# UARTSTM.net
KiCad netlist of a schematic drawn in Altium Designer
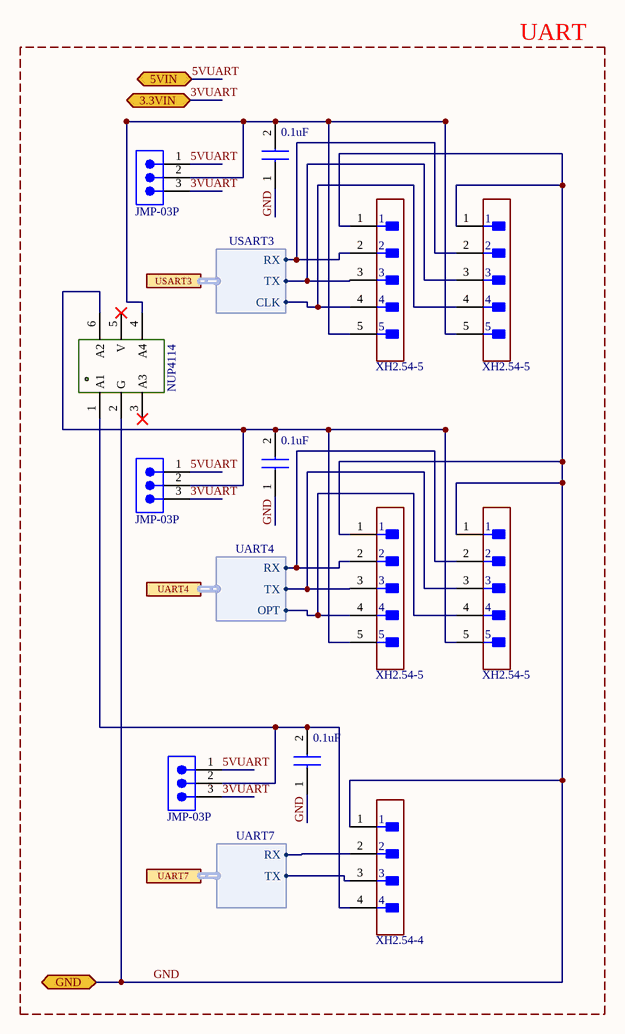
[diagram p0: UARTSTM.SchDoc]

(export (version "E")
  (design (tool "Eeschema 10.0.6"))
  (components
    (comp (ref "CAPUART3")
      (value "0.1uF")
      (footprint "CAP0805")
      (description "CAP-SMD0805")
      (libsource (lib "Components_Robots") (part "CAP0805"))
    )
    (comp (ref "CAPUART4")
      (value "0.1uF")
      (footprint "CAP0805")
      (description "CAP-SMD0805")
      (libsource (lib "Components_Robots") (part "CAP0805"))
    )
    (comp (ref "CAPUART7")
      (value "0.1uF")
      (footprint "CAP0805")
      (description "CAP-SMD0805")
      (libsource (lib "Components_Robots") (part "CAP0805"))
    )
    (comp (ref "JMPUART3")
      (value "JMP-03P")
      (footprint "JMP-03P")
      (description "PLS-1x3")
      (libsource (lib "Components_Robots") (part "JMP-03P"))
    )
    (comp (ref "JMPUART4")
      (value "JMP-03P")
      (footprint "JMP-03P")
      (description "PLS-1x3")
      (libsource (lib "Components_Robots") (part "JMP-03P"))
    )
    (comp (ref "JMPUART7")
      (value "JMP-03P")
      (footprint "JMP-03P")
      (description "PLS-1x3")
      (libsource (lib "Components_Robots") (part "JMP-03P"))
    )
    (comp (ref "NUPUART")
      (value "NUP4114")
      (footprint "NUP4114")
      (description "NUP4114HMR6T1G")
      (libsource (lib "Components_Robots") (part "NUP4114"))
    )
    (comp (ref "UART3-1")
      (value "XH2.54-5")
      (footprint "XH2.54-5")
      (description "JST XH2.54-5pin")
      (libsource (lib "Components_Robots") (part "XH2.54-5"))
    )
    (comp (ref "UART3-2")
      (value "XH2.54-5")
      (footprint "XH2.54-5")
      (description "JST XH2.54-5pin")
      (libsource (lib "Components_Robots") (part "XH2.54-5"))
    )
    (comp (ref "UART4-1")
      (value "XH2.54-5")
      (footprint "XH2.54-5")
      (description "JST XH2.54-5pin")
      (libsource (lib "Components_Robots") (part "XH2.54-5"))
    )
    (comp (ref "UART4-2")
      (value "XH2.54-5")
      (footprint "XH2.54-5")
      (description "JST XH2.54-5pin")
      (libsource (lib "Components_Robots") (part "XH2.54-5"))
    )
    (comp (ref "UART7-1")
      (value "XH2.54-4")
      (footprint "XH2.54-4")
      (description "JST XH2.54-4pin")
      (libsource (lib "Components_Robots") (part "XH2.54-4"))
    )
  )
  (nets
    (net (code "4") (name "/3VUART") (class "Default")
      (node (ref "JMPUART3") (pin "3") (pinfunction "3_3") (pintype "passive"))
      (node (ref "JMPUART4") (pin "3") (pinfunction "3_3") (pintype "passive"))
      (node (ref "JMPUART7") (pin "3") (pinfunction "3_3") (pintype "passive"))
    )
    (net (code "5") (name "/5VUART") (class "Default")
      (node (ref "JMPUART3") (pin "1") (pinfunction "1_1") (pintype "passive"))
      (node (ref "JMPUART4") (pin "1") (pinfunction "1_1") (pintype "passive"))
      (node (ref "JMPUART7") (pin "1") (pinfunction "1_1") (pintype "passive"))
    )
    (net (code "6") (name "/CLK") (class "Default")
      (node (ref "UART3-1") (pin "4") (pinfunction "4_4") (pintype "passive"))
      (node (ref "UART3-2") (pin "4") (pinfunction "4_4") (pintype "passive"))
    )
    (net (code "7") (name "/GND") (class "Default")
      (node (ref "CAPUART3") (pin "1") (pinfunction "1_1") (pintype "passive"))
      (node (ref "CAPUART4") (pin "1") (pinfunction "1_1") (pintype "passive"))
      (node (ref "CAPUART7") (pin "1") (pinfunction "1_1") (pintype "passive"))
      (node (ref "NUPUART") (pin "2") (pinfunction "G_2") (pintype "passive"))
      (node (ref "UART3-1") (pin "1") (pinfunction "1_1") (pintype "passive"))
      (node (ref "UART3-2") (pin "1") (pinfunction "1_1") (pintype "passive"))
      (node (ref "UART4-1") (pin "1") (pinfunction "1_1") (pintype "passive"))
      (node (ref "UART4-2") (pin "1") (pinfunction "1_1") (pintype "passive"))
      (node (ref "UART7-1") (pin "1") (pinfunction "1_1") (pintype "passive"))
    )
    (net (code "8") (name "/OPT") (class "Default")
      (node (ref "UART4-1") (pin "4") (pinfunction "4_4") (pintype "passive"))
      (node (ref "UART4-2") (pin "4") (pinfunction "4_4") (pintype "passive"))
    )
    (net (code "12") (name "Net-(NUPUART-A1)") (class "Default")
      (node (ref "CAPUART7") (pin "2") (pinfunction "2_2") (pintype "passive"))
      (node (ref "JMPUART7") (pin "2") (pinfunction "2_2") (pintype "passive"))
      (node (ref "NUPUART") (pin "1") (pinfunction "A1_1") (pintype "passive"))
      (node (ref "UART7-1") (pin "4") (pinfunction "4_4") (pintype "passive"))
    )
    (net (code "13") (name "Net-(NUPUART-A2)") (class "Default")
      (node (ref "CAPUART4") (pin "2") (pinfunction "2_2") (pintype "passive"))
      (node (ref "JMPUART4") (pin "2") (pinfunction "2_2") (pintype "passive"))
      (node (ref "NUPUART") (pin "6") (pinfunction "A2_6") (pintype "passive"))
      (node (ref "UART4-1") (pin "5") (pinfunction "5_5") (pintype "passive"))
      (node (ref "UART4-2") (pin "5") (pinfunction "5_5") (pintype "passive"))
    )
    (net (code "14") (name "Net-(NUPUART-A4)") (class "Default")
      (node (ref "CAPUART3") (pin "2") (pinfunction "2_2") (pintype "passive"))
      (node (ref "JMPUART3") (pin "2") (pinfunction "2_2") (pintype "passive"))
      (node (ref "NUPUART") (pin "4") (pinfunction "A4_4") (pintype "passive"))
      (node (ref "UART3-1") (pin "5") (pinfunction "5_5") (pintype "passive"))
      (node (ref "UART3-2") (pin "5") (pinfunction "5_5") (pintype "passive"))
    )
    (net (code "15") (name "Net-(UART3-1-Pad2)") (class "Default")
      (node (ref "UART3-1") (pin "2") (pinfunction "2_2") (pintype "passive"))
      (node (ref "UART3-2") (pin "2") (pinfunction "2_2") (pintype "passive"))
    )
    (net (code "16") (name "Net-(UART3-1-Pad3)") (class "Default")
      (node (ref "UART3-1") (pin "3") (pinfunction "3_3") (pintype "passive"))
      (node (ref "UART3-2") (pin "3") (pinfunction "3_3") (pintype "passive"))
    )
    (net (code "17") (name "Net-(UART4-1-Pad2)") (class "Default")
      (node (ref "UART4-1") (pin "2") (pinfunction "2_2") (pintype "passive"))
      (node (ref "UART4-2") (pin "2") (pinfunction "2_2") (pintype "passive"))
    )
    (net (code "18") (name "Net-(UART4-1-Pad3)") (class "Default")
      (node (ref "UART4-1") (pin "3") (pinfunction "3_3") (pintype "passive"))
      (node (ref "UART4-2") (pin "3") (pinfunction "3_3") (pintype "passive"))
    )
    (net (code "19") (name "unconnected-(NUPUART-A3-Pad3)") (class "Default")
      (node (ref "NUPUART") (pin "3") (pinfunction "A3_3") (pintype "passive+no_connect"))
    )
    (net (code "20") (name "unconnected-(NUPUART-V-Pad5)") (class "Default")
      (node (ref "NUPUART") (pin "5") (pinfunction "V_5") (pintype "passive+no_connect"))
    )
    (net (code "21") (name "unconnected-(UART7-1-Pad2)") (class "Default")
      (node (ref "UART7-1") (pin "2") (pinfunction "2_2") (pintype "passive"))
    )
    (net (code "22") (name "unconnected-(UART7-1-Pad3)") (class "Default")
      (node (ref "UART7-1") (pin "3") (pinfunction "3_3") (pintype "passive"))
    )
  )
)
